# 808_handclap.net
KiCad netlist of a schematic drawn in EAGLE
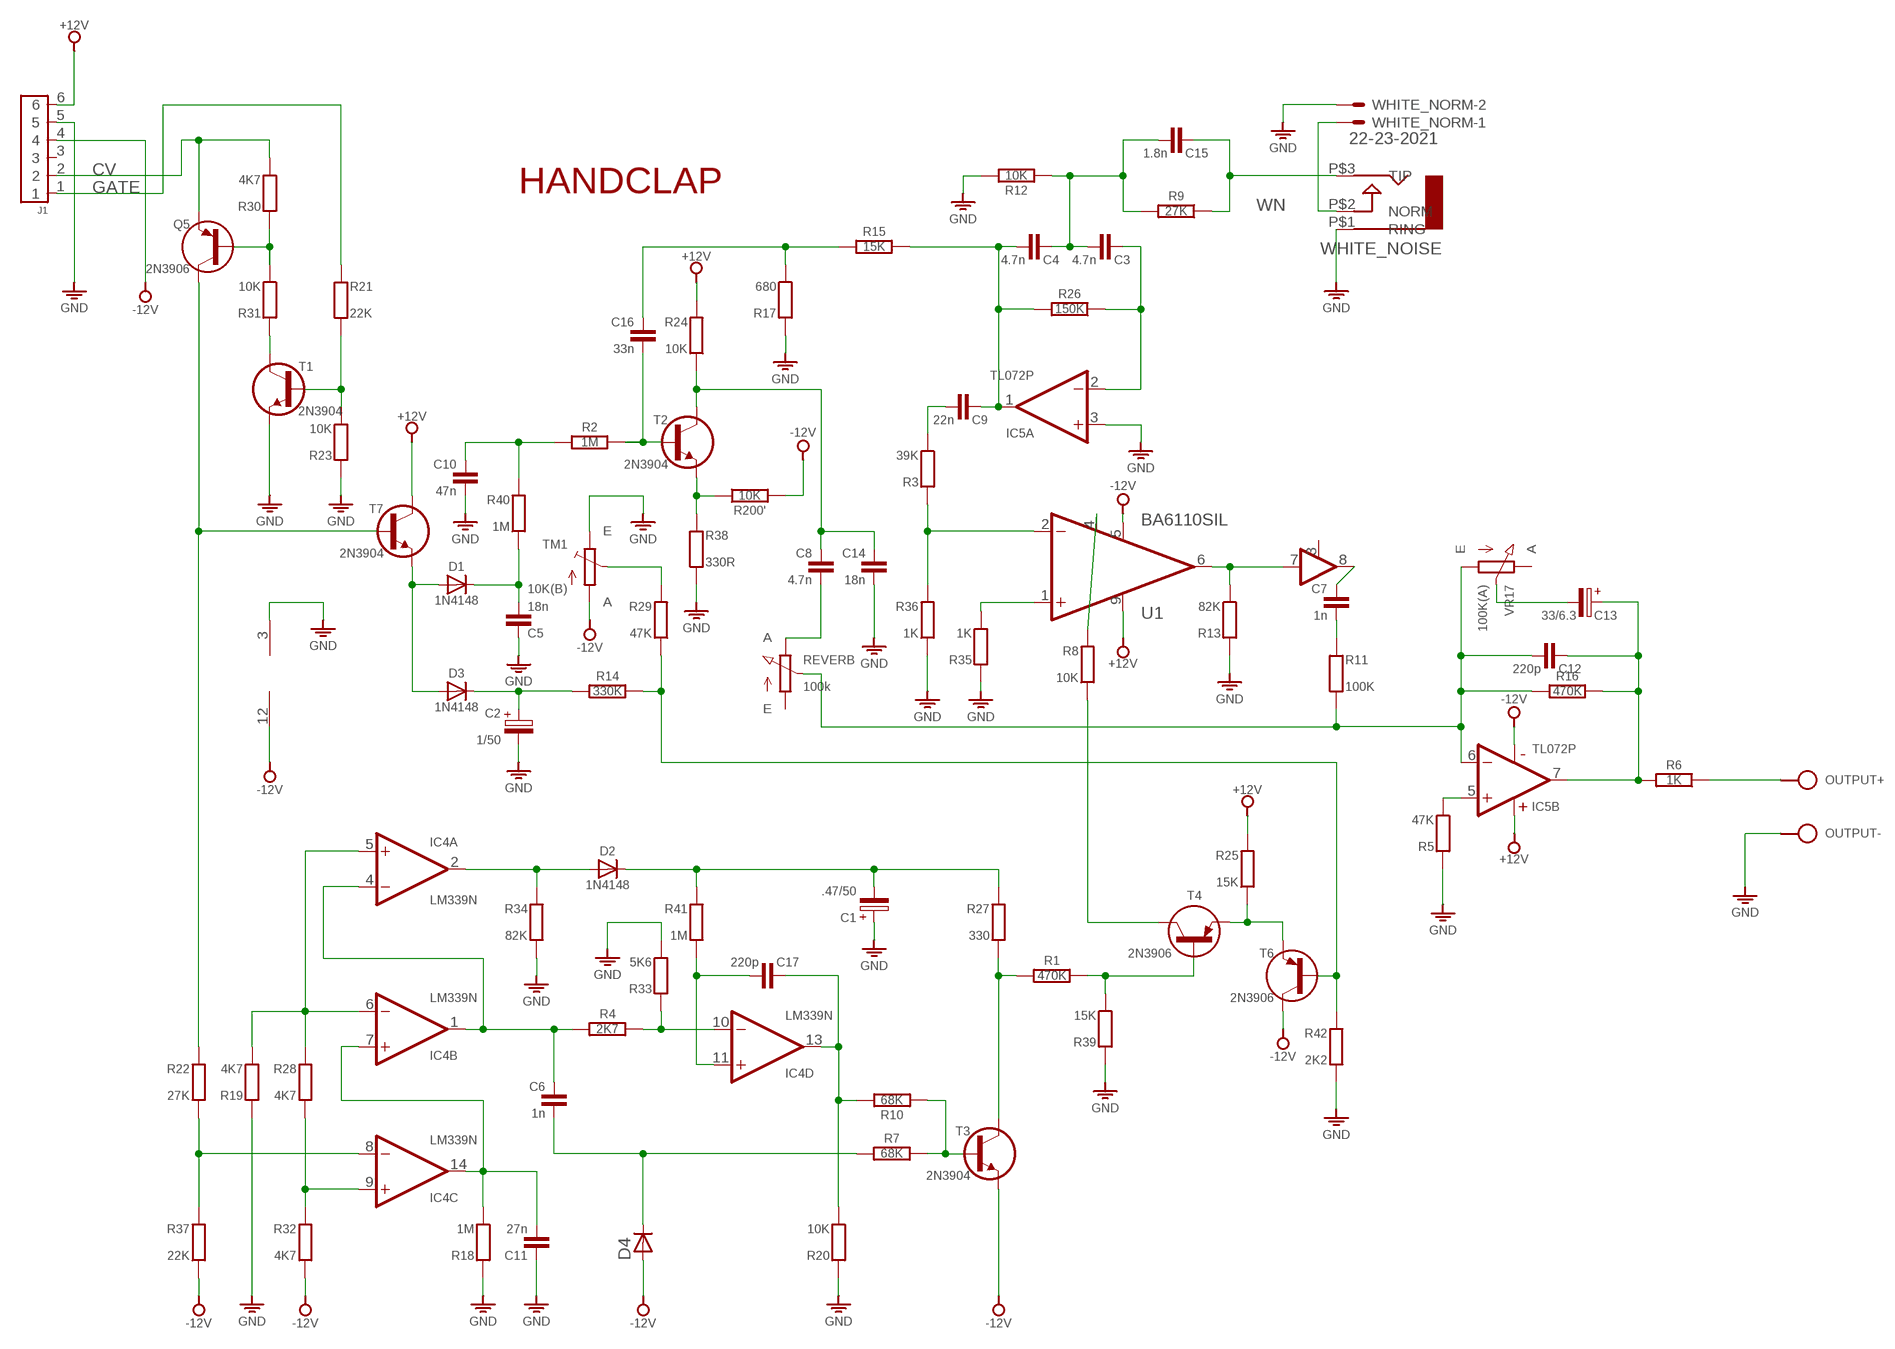
[diagram p0: schematic, sheet 1]

(export (version "E")
  (design (tool "Eeschema 10.0.6"))
  (components
    (comp (ref "C1")
      (value ".47/50")
      (footprint "eagle-import:E2,5-3_V")
      (libsource (lib "eagle-import") (part "CPOLE2,5-3/V"))
    )
    (comp (ref "C2")
      (value "1/50")
      (footprint "eagle-import:E2.5-4_V")
      (libsource (lib "eagle-import") (part "CPOLE2,5-4/V"))
    )
    (comp (ref "C3")
      (value "4.7n")
      (footprint "eagle-import:C050-020X044")
      (libsource (lib "eagle-import") (part "C-H050-020X044"))
    )
    (comp (ref "C4")
      (value "4.7n")
      (footprint "eagle-import:C050-020X044")
      (libsource (lib "eagle-import") (part "C-H050-020X044"))
    )
    (comp (ref "C5")
      (value "18n")
      (footprint "eagle-import:C050-020X044_V")
      (libsource (lib "eagle-import") (part "C050-020X044/V"))
    )
    (comp (ref "C6")
      (value "1n")
      (footprint "eagle-import:C050-020X044_V")
      (libsource (lib "eagle-import") (part "C050-020X044/V"))
    )
    (comp (ref "C7")
      (value "1n")
      (footprint "eagle-import:C050-020X044_V")
      (libsource (lib "eagle-import") (part "C050-020X044/V"))
    )
    (comp (ref "C8")
      (value "4.7n")
      (footprint "eagle-import:C050-020X044_V")
      (libsource (lib "eagle-import") (part "C050-020X044/V"))
    )
    (comp (ref "C9")
      (value "22n")
      (footprint "eagle-import:C050-020X044")
      (libsource (lib "eagle-import") (part "C-H050-020X044"))
    )
    (comp (ref "C10")
      (value "47n")
      (footprint "eagle-import:C050-020X044_V")
      (libsource (lib "eagle-import") (part "C050-020X044/V"))
    )
    (comp (ref "C11")
      (value "27n")
      (footprint "eagle-import:C050-020X044_V")
      (libsource (lib "eagle-import") (part "C050-020X044/V"))
    )
    (comp (ref "C12")
      (value "220p")
      (footprint "eagle-import:C050-020X044")
      (libsource (lib "eagle-import") (part "C-H050-020X044"))
    )
    (comp (ref "C13")
      (value "33/6.3")
      (footprint "eagle-import:E2,5-3")
      (libsource (lib "eagle-import") (part "CPOL-HE2,5-3"))
    )
    (comp (ref "C14")
      (value "18n")
      (footprint "eagle-import:C050-020X044_V")
      (libsource (lib "eagle-import") (part "C050-020X044/V"))
    )
    (comp (ref "C15")
      (value "1.8n")
      (footprint "eagle-import:C050-020X044")
      (libsource (lib "eagle-import") (part "C-H050-020X044"))
    )
    (comp (ref "C16")
      (value "33n")
      (footprint "eagle-import:C050-020X044_V")
      (libsource (lib "eagle-import") (part "C050-020X044/V"))
    )
    (comp (ref "C17")
      (value "220p")
      (footprint "eagle-import:C050-020X044")
      (libsource (lib "eagle-import") (part "C-H050-020X044"))
    )
    (comp (ref "D1")
      (value "1N4148")
      (footprint "eagle-import:DO34-10")
      (libsource (lib "eagle-import") (part "DIODE-HDO34-10"))
    )
    (comp (ref "D2")
      (value "1N4148")
      (footprint "eagle-import:DO34-10")
      (libsource (lib "eagle-import") (part "DIODE-HDO34-10"))
    )
    (comp (ref "D3")
      (value "1N4148")
      (footprint "eagle-import:DO34-10")
      (libsource (lib "eagle-import") (part "DIODE-HDO34-10"))
    )
    (comp (ref "D4")
      (value "1N4148DO35-7")
      (footprint "eagle-import:DO35-7")
      (libsource (lib "eagle-import") (part "1N4148DO35-7"))
    )
    (comp (ref "IC3")
      (value "LM339N")
      (footprint "eagle-import:DIL14")
      (libsource (lib "eagle-import") (part "linear_LM339N"))
    )
    (comp (ref "IC4")
      (value "LM339N")
      (footprint "eagle-import:DIL14")
      (libsource (lib "eagle-import") (part "LM339N"))
    )
    (comp (ref "IC5")
      (value "TL072P")
      (footprint "eagle-import:DIL08")
      (libsource (lib "eagle-import") (part "TL072P"))
    )
    (comp (ref "J1")
      (value "CONN-6P")
      (footprint "eagle-import:CONN-6P")
      (libsource (lib "eagle-import") (part "CONN-6P"))
    )
    (comp (ref "OUTPUT")
      (value "SPAD+-+-")
      (footprint "eagle-import:SPAD+-")
      (libsource (lib "eagle-import") (part "SPAD+-+-"))
    )
    (comp (ref "Q5")
      (value "2N3906")
      (footprint "eagle-import:TO92")
      (libsource (lib "eagle-import") (part "2N3906"))
    )
    (comp (ref "R1")
      (value "470K")
      (footprint "eagle-import:0204_10")
      (libsource (lib "eagle-import") (part "R-H0204/10"))
    )
    (comp (ref "R2")
      (value "1M")
      (footprint "eagle-import:0204_10")
      (libsource (lib "eagle-import") (part "R-H0204/10"))
    )
    (comp (ref "R3")
      (value "39K")
      (footprint "eagle-import:0204_10-V")
      (libsource (lib "eagle-import") (part "R0204/10-V"))
    )
    (comp (ref "R4")
      (value "2K7")
      (footprint "eagle-import:0204_10")
      (libsource (lib "eagle-import") (part "R-H0204/10"))
    )
    (comp (ref "R5")
      (value "47K")
      (footprint "eagle-import:0204_10-V")
      (libsource (lib "eagle-import") (part "R0204/10-V"))
    )
    (comp (ref "R6")
      (value "1K")
      (footprint "eagle-import:0204_10")
      (libsource (lib "eagle-import") (part "R-H0204/10"))
    )
    (comp (ref "R7")
      (value "68K")
      (footprint "eagle-import:0204_10")
      (libsource (lib "eagle-import") (part "R-H0204/10"))
    )
    (comp (ref "R8")
      (value "10K")
      (footprint "eagle-import:0204_10-V")
      (libsource (lib "eagle-import") (part "R0204/10-V"))
    )
    (comp (ref "R9")
      (value "27K")
      (footprint "eagle-import:0204_10")
      (libsource (lib "eagle-import") (part "R-H0204/10"))
    )
    (comp (ref "R10")
      (value "68K")
      (footprint "eagle-import:0204_10")
      (libsource (lib "eagle-import") (part "R-H0204/10"))
    )
    (comp (ref "R11")
      (value "100K")
      (footprint "eagle-import:0204_10-V")
      (libsource (lib "eagle-import") (part "R0204/10-V"))
    )
    (comp (ref "R12")
      (value "10K")
      (footprint "eagle-import:0204_10")
      (libsource (lib "eagle-import") (part "R-H0204/10"))
    )
    (comp (ref "R13")
      (value "82K")
      (footprint "eagle-import:0204_10-V")
      (libsource (lib "eagle-import") (part "R0204/10-V"))
    )
    (comp (ref "R14")
      (value "330K")
      (footprint "eagle-import:0204_10")
      (libsource (lib "eagle-import") (part "R-H0204/10"))
    )
    (comp (ref "R15")
      (value "15K")
      (footprint "eagle-import:0204_10")
      (libsource (lib "eagle-import") (part "R-H0204/10"))
    )
    (comp (ref "R16")
      (value "470K")
      (footprint "eagle-import:0204_10")
      (libsource (lib "eagle-import") (part "R-H0204/10"))
    )
    (comp (ref "R17")
      (value "680")
      (footprint "eagle-import:0204_10-V")
      (libsource (lib "eagle-import") (part "R0204/10-V"))
    )
    (comp (ref "R18")
      (value "1M")
      (footprint "eagle-import:0204_10-V")
      (libsource (lib "eagle-import") (part "R0204/10-V"))
    )
    (comp (ref "R19")
      (value "4K7")
      (footprint "eagle-import:0204_10-V")
      (libsource (lib "eagle-import") (part "R0204/10-V"))
    )
    (comp (ref "R20")
      (value "10K")
      (footprint "eagle-import:0204_10-V")
      (libsource (lib "eagle-import") (part "R0204/10-V"))
    )
    (comp (ref "R21")
      (value "22K")
      (footprint "eagle-import:0204_10-V")
      (libsource (lib "eagle-import") (part "R0204/10-V"))
    )
    (comp (ref "R22")
      (value "27K")
      (footprint "eagle-import:0204_10-V")
      (libsource (lib "eagle-import") (part "R0204/10-V"))
    )
    (comp (ref "R23")
      (value "10K")
      (footprint "eagle-import:0204_10-V")
      (libsource (lib "eagle-import") (part "R0204/10-V"))
    )
    (comp (ref "R24")
      (value "10K")
      (footprint "eagle-import:0204_10-V")
      (libsource (lib "eagle-import") (part "R0204/10-V"))
    )
    (comp (ref "R25")
      (value "15K")
      (footprint "eagle-import:0204_10-V")
      (libsource (lib "eagle-import") (part "R0204/10-V"))
    )
    (comp (ref "R26")
      (value "150K")
      (footprint "eagle-import:0204_10")
      (libsource (lib "eagle-import") (part "R-H0204/10"))
    )
    (comp (ref "R27")
      (value "330")
      (footprint "eagle-import:0204_10-V")
      (libsource (lib "eagle-import") (part "R0204/10-V"))
    )
    (comp (ref "R28")
      (value "4K7")
      (footprint "eagle-import:0204_10-V")
      (libsource (lib "eagle-import") (part "R0204/10-V"))
    )
    (comp (ref "R29")
      (value "47K")
      (footprint "eagle-import:0204_10-V")
      (libsource (lib "eagle-import") (part "R0204/10-V"))
    )
    (comp (ref "R30")
      (value "4K7")
      (footprint "eagle-import:0204_10-V")
      (libsource (lib "eagle-import") (part "R0204/10-V"))
    )
    (comp (ref "R31")
      (value "10K")
      (footprint "eagle-import:0204_10-V")
      (libsource (lib "eagle-import") (part "R0204/10-V"))
    )
    (comp (ref "R32")
      (value "4K7")
      (footprint "eagle-import:0204_10-V")
      (libsource (lib "eagle-import") (part "R0204/10-V"))
    )
    (comp (ref "R33")
      (value "5K6")
      (footprint "eagle-import:0204_10-V")
      (libsource (lib "eagle-import") (part "R0204/10-V"))
    )
    (comp (ref "R34")
      (value "82K")
      (footprint "eagle-import:0204_10-V")
      (libsource (lib "eagle-import") (part "R0204/10-V"))
    )
    (comp (ref "R35")
      (value "1K")
      (footprint "eagle-import:0204_10-V")
      (libsource (lib "eagle-import") (part "R0204/10-V"))
    )
    (comp (ref "R36")
      (value "1K")
      (footprint "eagle-import:0204_10-V")
      (libsource (lib "eagle-import") (part "R0204/10-V"))
    )
    (comp (ref "R37")
      (value "22K")
      (footprint "eagle-import:0204_10-V")
      (libsource (lib "eagle-import") (part "R0204/10-V"))
    )
    (comp (ref "R38")
      (value "330R")
      (footprint "eagle-import:0204_10-V")
      (libsource (lib "eagle-import") (part "R0204/10-V"))
    )
    (comp (ref "R39")
      (value "15K")
      (footprint "eagle-import:0204_10-V")
      (libsource (lib "eagle-import") (part "R0204/10-V"))
    )
    (comp (ref "R40")
      (value "1M")
      (footprint "eagle-import:0204_10-V")
      (libsource (lib "eagle-import") (part "R0204/10-V"))
    )
    (comp (ref "R41")
      (value "1M")
      (footprint "eagle-import:0204_10-V")
      (libsource (lib "eagle-import") (part "R0204/10-V"))
    )
    (comp (ref "R42")
      (value "2K2")
      (footprint "eagle-import:0204_10-V")
      (libsource (lib "eagle-import") (part "R0204/10-V"))
    )
    (comp (ref "R200'")
      (value "10K")
      (footprint "eagle-import:0204_10")
      (libsource (lib "eagle-import") (part "R-H0204/10"))
    )
    (comp (ref "REVERB")
      (value "100k")
      (footprint "eagle-import:POT")
      (libsource (lib "eagle-import") (part "POT"))
    )
    (comp (ref "T1")
      (value "2N3904")
      (footprint "eagle-import:TO92")
      (libsource (lib "eagle-import") (part "2N3904"))
    )
    (comp (ref "T2")
      (value "2N3904")
      (footprint "eagle-import:TO92")
      (libsource (lib "eagle-import") (part "2N3904"))
    )
    (comp (ref "T3")
      (value "2N3904")
      (footprint "eagle-import:TO92")
      (libsource (lib "eagle-import") (part "2N3904"))
    )
    (comp (ref "T4")
      (value "2N3906")
      (footprint "eagle-import:TO92")
      (libsource (lib "eagle-import") (part "2N3906-H"))
    )
    (comp (ref "T6")
      (value "2N3906")
      (footprint "eagle-import:TO92")
      (libsource (lib "eagle-import") (part "2N3906"))
    )
    (comp (ref "T7")
      (value "2N3904")
      (footprint "eagle-import:TO92")
      (libsource (lib "eagle-import") (part "2N3904"))
    )
    (comp (ref "TM1")
      (value "10K(B)")
      (footprint "eagle-import:R-TRIM")
      (libsource (lib "eagle-import") (part "TRIMR-TRIM"))
    )
    (comp (ref "U1")
      (value "BA6110SIL")
      (footprint "eagle-import:SIL09")
      (libsource (lib "eagle-import") (part "BA6110SIL"))
    )
    (comp (ref "VR17")
      (value "100K(A)")
      (footprint "eagle-import:POT")
      (libsource (lib "eagle-import") (part "POT"))
    )
    (comp (ref "WHITE_NOISE")
      (value "AUDIO-JACK")
      (footprint "eagle-import:ERTHENVAR-JACK-90DEG")
      (libsource (lib "eagle-import") (part "AUDIO-JACK"))
    )
    (comp (ref "WHITE_NORM")
      (value "22-23-2021")
      (footprint "eagle-import:22-23-2021")
      (fields (field (name "MF") "MOLEX"))
      (libsource (lib "eagle-import") (part "22-23-2021"))
    )
  )
  (nets
    (net (code "1") (name "+12V") (class "Default")
      (node (ref "IC5") (pin "8") (pinfunction "V+_8") (pintype "power_in"))
      (node (ref "J1") (pin "6") (pinfunction "6_6") (pintype "bidirectional"))
      (node (ref "R24") (pin "1") (pinfunction "1_1") (pintype "passive"))
      (node (ref "R25") (pin "1") (pinfunction "1_1") (pintype "passive"))
      (node (ref "T7") (pin "3") (pinfunction "C_3") (pintype "passive"))
      (node (ref "U1") (pin "9") (pinfunction "V+_9") (pintype "bidirectional"))
    )
    (net (code "2") (name "-12V") (class "Default")
      (node (ref "D4") (pin "A") (pinfunction "A_A") (pintype "passive"))
      (node (ref "IC3") (pin "12") (pinfunction "GND_12") (pintype "power_in"))
      (node (ref "IC5") (pin "4") (pinfunction "V-_4") (pintype "power_in"))
      (node (ref "J1") (pin "4") (pinfunction "4_4") (pintype "bidirectional"))
      (node (ref "R200'") (pin "2") (pinfunction "2_2") (pintype "passive"))
      (node (ref "R32") (pin "2") (pinfunction "2_2") (pintype "passive"))
      (node (ref "R37") (pin "2") (pinfunction "2_2") (pintype "passive"))
      (node (ref "T3") (pin "1") (pinfunction "E_1") (pintype "passive"))
      (node (ref "T6") (pin "3") (pinfunction "C_3") (pintype "passive"))
      (node (ref "TM1") (pin "1") (pinfunction "A_1") (pintype "passive"))
      (node (ref "U1") (pin "5") (pinfunction "V-_5") (pintype "bidirectional"))
    )
    (net (code "3") (name "/CV") (class "Default")
      (node (ref "J1") (pin "2") (pinfunction "2_2") (pintype "bidirectional"))
      (node (ref "Q5") (pin "1") (pinfunction "E_1") (pintype "passive"))
      (node (ref "R30") (pin "2") (pinfunction "2_2") (pintype "passive"))
    )
    (net (code "4") (name "/GATE") (class "Default")
      (node (ref "J1") (pin "1") (pinfunction "1_1") (pintype "bidirectional"))
      (node (ref "R21") (pin "1") (pinfunction "1_1") (pintype "passive"))
    )
    (net (code "5") (name "/WN") (class "Default")
      (node (ref "C15") (pin "1") (pinfunction "1_1") (pintype "passive"))
      (node (ref "R9") (pin "1") (pinfunction "1_1") (pintype "passive"))
      (node (ref "WHITE_NOISE") (pin "P$3") (pinfunction "TIP_P$3") (pintype "bidirectional"))
    )
    (net (code "6") (name "GND") (class "Default")
      (node (ref "C1") (pin "+") (pinfunction "+_+") (pintype "passive"))
      (node (ref "C10") (pin "2") (pinfunction "2_2") (pintype "passive"))
      (node (ref "C11") (pin "1") (pinfunction "1_1") (pintype "passive"))
      (node (ref "C14") (pin "2") (pinfunction "2_2") (pintype "passive"))
      (node (ref "C2") (pin "-") (pinfunction "-_-") (pintype "passive"))
      (node (ref "C5") (pin "1") (pinfunction "1_1") (pintype "passive"))
      (node (ref "IC3") (pin "3") (pinfunction "V+_3") (pintype "power_in"))
      (node (ref "IC5") (pin "3") (pinfunction "+IN_3") (pintype "input"))
      (node (ref "J1") (pin "5") (pinfunction "5_5") (pintype "bidirectional"))
      (node (ref "OUTPUT") (pin "1") (pinfunction "P$1_1") (pintype "passive"))
      (node (ref "R12") (pin "1") (pinfunction "1_1") (pintype "passive"))
      (node (ref "R13") (pin "1") (pinfunction "1_1") (pintype "passive"))
      (node (ref "R17") (pin "1") (pinfunction "1_1") (pintype "passive"))
      (node (ref "R18") (pin "1") (pinfunction "1_1") (pintype "passive"))
      (node (ref "R19") (pin "1") (pinfunction "1_1") (pintype "passive"))
      (node (ref "R20") (pin "1") (pinfunction "1_1") (pintype "passive"))
      (node (ref "R23") (pin "1") (pinfunction "1_1") (pintype "passive"))
      (node (ref "R33") (pin "2") (pinfunction "2_2") (pintype "passive"))
      (node (ref "R34") (pin "2") (pinfunction "2_2") (pintype "passive"))
      (node (ref "R35") (pin "1") (pinfunction "1_1") (pintype "passive"))
      (node (ref "R36") (pin "2") (pinfunction "2_2") (pintype "passive"))
      (node (ref "R38") (pin "2") (pinfunction "2_2") (pintype "passive"))
      (node (ref "R39") (pin "1") (pinfunction "1_1") (pintype "passive"))
      (node (ref "R42") (pin "2") (pinfunction "2_2") (pintype "passive"))
      (node (ref "R5") (pin "1") (pinfunction "1_1") (pintype "passive"))
      (node (ref "T1") (pin "1") (pinfunction "E_1") (pintype "passive"))
      (node (ref "TM1") (pin "3") (pinfunction "E_3") (pintype "passive"))
      (node (ref "WHITE_NOISE") (pin "P$1") (pinfunction "RING_P$1") (pintype "bidirectional"))
      (node (ref "WHITE_NORM") (pin "2") (pinfunction "S_2") (pintype "passive"))
    )
    (net (code "7") (name "Net-(C1-Pad-)") (class "Default")
      (node (ref "C1") (pin "-") (pinfunction "-_-") (pintype "passive"))
      (node (ref "D2") (pin "C") (pinfunction "C_C") (pintype "passive"))
      (node (ref "R27") (pin "1") (pinfunction "1_1") (pintype "passive"))
      (node (ref "R41") (pin "1") (pinfunction "1_1") (pintype "passive"))
    )
    (net (code "8") (name "Net-(C2-Pad+)") (class "Default")
      (node (ref "C2") (pin "+") (pinfunction "+_+") (pintype "passive"))
      (node (ref "D3") (pin "C") (pinfunction "C_C") (pintype "passive"))
      (node (ref "R14") (pin "2") (pinfunction "2_2") (pintype "passive"))
    )
    (net (code "9") (name "Net-(C5-Pad2)") (class "Default")
      (node (ref "C5") (pin "2") (pinfunction "2_2") (pintype "passive"))
      (node (ref "D1") (pin "C") (pinfunction "C_C") (pintype "passive"))
      (node (ref "R40") (pin "2") (pinfunction "2_2") (pintype "passive"))
    )
    (net (code "10") (name "Net-(C6-Pad2)") (class "Default")
      (node (ref "C6") (pin "2") (pinfunction "2_2") (pintype "passive"))
      (node (ref "D4") (pin "C") (pinfunction "C_C") (pintype "passive"))
      (node (ref "R7") (pin "2") (pinfunction "2_2") (pintype "passive"))
    )
    (net (code "11") (name "Net-(C7-Pad2)") (class "Default")
      (node (ref "C7") (pin "2") (pinfunction "2_2") (pintype "passive"))
      (node (ref "R11") (pin "1") (pinfunction "1_1") (pintype "passive"))
    )
    (net (code "12") (name "Net-(C8-Pad2)") (class "Default")
      (node (ref "C8") (pin "2") (pinfunction "2_2") (pintype "passive"))
      (node (ref "REVERB") (pin "E") (pinfunction "E_E") (pintype "passive"))
    )
    (net (code "13") (name "Net-(C9-Pad2)") (class "Default")
      (node (ref "C9") (pin "2") (pinfunction "2_2") (pintype "passive"))
      (node (ref "R3") (pin "2") (pinfunction "2_2") (pintype "passive"))
    )
    (net (code "14") (name "Net-(C10-Pad1)") (class "Default")
      (node (ref "C10") (pin "1") (pinfunction "1_1") (pintype "passive"))
      (node (ref "R2") (pin "2") (pinfunction "2_2") (pintype "passive"))
      (node (ref "R40") (pin "1") (pinfunction "1_1") (pintype "passive"))
    )
    (net (code "15") (name "Net-(C13-Pad-)") (class "Default")
      (node (ref "C13") (pin "-") (pinfunction "-_-") (pintype "passive"))
      (node (ref "VR17") (pin "S") (pinfunction "S_S") (pintype "passive"))
    )
    (net (code "16") (name "Net-(C15-Pad2)") (class "Default")
      (node (ref "C15") (pin "2") (pinfunction "2_2") (pintype "passive"))
      (node (ref "C3") (pin "2") (pinfunction "2_2") (pintype "passive"))
      (node (ref "C4") (pin "1") (pinfunction "1_1") (pintype "passive"))
      (node (ref "R12") (pin "2") (pinfunction "2_2") (pintype "passive"))
      (node (ref "R9") (pin "2") (pinfunction "2_2") (pintype "passive"))
    )
    (net (code "17") (name "Net-(C16-Pad1)") (class "Default")
      (node (ref "C16") (pin "1") (pinfunction "1_1") (pintype "passive"))
      (node (ref "R15") (pin "2") (pinfunction "2_2") (pintype "passive"))
      (node (ref "R17") (pin "2") (pinfunction "2_2") (pintype "passive"))
    )
    (net (code "18") (name "Net-(IC4B-+IN)") (class "Default")
      (node (ref "IC4") (pin "5") (pinfunction "+IN_5") (pintype "input"))
      (node (ref "IC4") (pin "6") (pinfunction "-IN_6") (pintype "input"))
      (node (ref "R19") (pin "2") (pinfunction "2_2") (pintype "passive"))
      (node (ref "R28") (pin "1") (pinfunction "1_1") (pintype "passive"))
    )
    (net (code "19") (name "Net-(IC4B--IN)") (class "Default")
      (node (ref "C6") (pin "1") (pinfunction "1_1") (pintype "passive"))
      (node (ref "IC4") (pin "1") (pinfunction "OUT_1") (pintype "output"))
      (node (ref "IC4") (pin "4") (pinfunction "-IN_4") (pintype "input"))
      (node (ref "R4") (pin "2") (pinfunction "2_2") (pintype "passive"))
    )
    (net (code "20") (name "Net-(IC4B-OUT)") (class "Default")
      (node (ref "D2") (pin "A") (pinfunction "A_A") (pintype "passive"))
      (node (ref "IC4") (pin "2") (pinfunction "OUT_2") (pintype "output"))
      (node (ref "R34") (pin "1") (pinfunction "1_1") (pintype "passive"))
    )
    (net (code "21") (name "Net-(IC4C-+IN)") (class "Default")
      (node (ref "C11") (pin "2") (pinfunction "2_2") (pintype "passive"))
      (node (ref "IC4") (pin "14") (pinfunction "OUT_14") (pintype "output"))
      (node (ref "IC4") (pin "7") (pinfunction "+IN_7") (pintype "input"))
      (node (ref "R18") (pin "2") (pinfunction "2_2") (pintype "passive"))
    )
    (net (code "22") (name "Net-(IC4D-+IN)") (class "Default")
      (node (ref "IC4") (pin "9") (pinfunction "+IN_9") (pintype "input"))
      (node (ref "R28") (pin "2") (pinfunction "2_2") (pintype "passive"))
      (node (ref "R32") (pin "1") (pinfunction "1_1") (pintype "passive"))
    )
    (net (code "23") (name "Net-(IC4D--IN)") (class "Default")
      (node (ref "IC4") (pin "8") (pinfunction "-IN_8") (pintype "input"))
      (node (ref "R22") (pin "2") (pinfunction "2_2") (pintype "passive"))
      (node (ref "R37") (pin "1") (pinfunction "1_1") (pintype "passive"))
    )
    (net (code "24") (name "Net-(IC4E-+IN)") (class "Default")
      (node (ref "C17") (pin "2") (pinfunction "2_2") (pintype "passive"))
      (node (ref "IC4") (pin "11") (pinfunction "+IN_11") (pintype "input"))
      (node (ref "R41") (pin "2") (pinfunction "2_2") (pintype "passive"))
    )
    (net (code "25") (name "Net-(IC4E--IN)") (class "Default")
      (node (ref "IC4") (pin "10") (pinfunction "-IN_10") (pintype "input"))
      (node (ref "R33") (pin "1") (pinfunction "1_1") (pintype "passive"))
      (node (ref "R4") (pin "1") (pinfunction "1_1") (pintype "passive"))
    )
    (net (code "26") (name "Net-(IC4E-OUT)") (class "Default")
      (node (ref "C17") (pin "1") (pinfunction "1_1") (pintype "passive"))
      (node (ref "IC4") (pin "13") (pinfunction "OUT_13") (pintype "output"))
      (node (ref "R10") (pin "1") (pinfunction "1_1") (pintype "passive"))
      (node (ref "R20") (pin "2") (pinfunction "2_2") (pintype "passive"))
    )
    (net (code "27") (name "Net-(IC5A--IN)") (class "Default")
      (node (ref "C3") (pin "1") (pinfunction "1_1") (pintype "passive"))
      (node (ref "IC5") (pin "2") (pinfunction "-IN_2") (pintype "input"))
      (node (ref "R26") (pin "1") (pinfunction "1_1") (pintype "passive"))
    )
    (net (code "28") (name "Net-(IC5A-OUT)") (class "Default")
      (node (ref "C4") (pin "2") (pinfunction "2_2") (pintype "passive"))
      (node (ref "C9") (pin "1") (pinfunction "1_1") (pintype "passive"))
      (node (ref "IC5") (pin "1") (pinfunction "OUT_1") (pintype "output"))
      (node (ref "R15") (pin "1") (pinfunction "1_1") (pintype "passive"))
      (node (ref "R26") (pin "2") (pinfunction "2_2") (pintype "passive"))
    )
    (net (code "29") (name "Net-(IC5B-+IN)") (class "Default")
      (node (ref "IC5") (pin "5") (pinfunction "+IN_5") (pintype "input"))
      (node (ref "R5") (pin "2") (pinfunction "2_2") (pintype "passive"))
    )
    (net (code "30") (name "Net-(IC5B--IN)") (class "Default")
      (node (ref "C12") (pin "2") (pinfunction "2_2") (pintype "passive"))
      (node (ref "IC5") (pin "6") (pinfunction "-IN_6") (pintype "input"))
      (node (ref "R11") (pin "2") (pinfunction "2_2") (pintype "passive"))
      (node (ref "R16") (pin "2") (pinfunction "2_2") (pintype "passive"))
      (node (ref "REVERB") (pin "S") (pinfunction "S_S") (pintype "passive"))
      (node (ref "VR17") (pin "A") (pinfunction "A_A") (pintype "passive"))
    )
    (net (code "31") (name "Net-(IC5B-OUT)") (class "Default")
      (node (ref "C12") (pin "1") (pinfunction "1_1") (pintype "passive"))
      (node (ref "C13") (pin "+") (pinfunction "+_+") (pintype "passive"))
      (node (ref "IC5") (pin "7") (pinfunction "OUT_7") (pintype "output"))
      (node (ref "R16") (pin "1") (pinfunction "1_1") (pintype "passive"))
      (node (ref "R6") (pin "2") (pinfunction "2_2") (pintype "passive"))
    )
    (net (code "32") (name "Net-(OUTPUTA-P$1)") (class "Default")
      (node (ref "OUTPUT") (pin "2") (pinfunction "P$1_2") (pintype "passive"))
      (node (ref "R6") (pin "1") (pinfunction "1_1") (pintype "passive"))
    )
    (net (code "33") (name "Net-(Q5-B)") (class "Default")
      (node (ref "Q5") (pin "2") (pinfunction "B_2") (pintype "passive"))
      (node (ref "R30") (pin "1") (pinfunction "1_1") (pintype "passive"))
      (node (ref "R31") (pin "2") (pinfunction "2_2") (pintype "passive"))
    )
    (net (code "34") (name "Net-(Q5-C)") (class "Default")
      (node (ref "Q5") (pin "3") (pinfunction "C_3") (pintype "passive"))
      (node (ref "R22") (pin "1") (pinfunction "1_1") (pintype "passive"))
      (node (ref "T7") (pin "2") (pinfunction "B_2") (pintype "passive"))
    )
    (net (code "35") (name "Net-(T1-B)") (class "Default")
      (node (ref "R21") (pin "2") (pinfunction "2_2") (pintype "passive"))
      (node (ref "R23") (pin "2") (pinfunction "2_2") (pintype "passive"))
      (node (ref "T1") (pin "2") (pinfunction "B_2") (pintype "passive"))
    )
    (net (code "36") (name "Net-(T1-C)") (class "Default")
      (node (ref "R31") (pin "1") (pinfunction "1_1") (pintype "passive"))
      (node (ref "T1") (pin "3") (pinfunction "C_3") (pintype "passive"))
    )
    (net (code "37") (name "Net-(T2-B)") (class "Default")
      (node (ref "C16") (pin "2") (pinfunction "2_2") (pintype "passive"))
      (node (ref "R2") (pin "1") (pinfunction "1_1") (pintype "passive"))
      (node (ref "T2") (pin "2") (pinfunction "B_2") (pintype "passive"))
    )
    (net (code "38") (name "Net-(T2-C)") (class "Default")
      (node (ref "C14") (pin "1") (pinfunction "1_1") (pintype "passive"))
      (node (ref "C8") (pin "1") (pinfunction "1_1") (pintype "passive"))
      (node (ref "R24") (pin "2") (pinfunction "2_2") (pintype "passive"))
      (node (ref "T2") (pin "3") (pinfunction "C_3") (pintype "passive"))
    )
    (net (code "39") (name "Net-(T2-E)") (class "Default")
      (node (ref "R200'") (pin "1") (pinfunction "1_1") (pintype "passive"))
      (node (ref "R38") (pin "1") (pinfunction "1_1") (pintype "passive"))
      (node (ref "T2") (pin "1") (pinfunction "E_1") (pintype "passive"))
    )
    (net (code "40") (name "Net-(T3-B)") (class "Default")
      (node (ref "R10") (pin "2") (pinfunction "2_2") (pintype "passive"))
      (node (ref "R7") (pin "1") (pinfunction "1_1") (pintype "passive"))
      (node (ref "T3") (pin "2") (pinfunction "B_2") (pintype "passive"))
    )
    (net (code "41") (name "Net-(T3-C)") (class "Default")
      (node (ref "R1") (pin "2") (pinfunction "2_2") (pintype "passive"))
      (node (ref "R27") (pin "2") (pinfunction "2_2") (pintype "passive"))
      (node (ref "T3") (pin "3") (pinfunction "C_3") (pintype "passive"))
    )
    (net (code "42") (name "Net-(T4-B)") (class "Default")
      (node (ref "R1") (pin "1") (pinfunction "1_1") (pintype "passive"))
      (node (ref "R39") (pin "2") (pinfunction "2_2") (pintype "passive"))
      (node (ref "T4") (pin "2") (pinfunction "B_2") (pintype "passive"))
    )
    (net (code "43") (name "Net-(T4-C)") (class "Default")
      (node (ref "R8") (pin "2") (pinfunction "2_2") (pintype "passive"))
      (node (ref "T4") (pin "3") (pinfunction "C_3") (pintype "passive"))
    )
    (net (code "44") (name "Net-(T4-E)") (class "Default")
      (node (ref "R25") (pin "2") (pinfunction "2_2") (pintype "passive"))
      (node (ref "T4") (pin "1") (pinfunction "E_1") (pintype "passive"))
      (node (ref "T6") (pin "1") (pinfunction "E_1") (pintype "passive"))
    )
    (net (code "45") (name "Net-(T6-B)") (class "Default")
      (node (ref "R14") (pin "1") (pinfunction "1_1") (pintype "passive"))
      (node (ref "R29") (pin "2") (pinfunction "2_2") (pintype "passive"))
      (node (ref "R42") (pin "1") (pinfunction "1_1") (pintype "passive"))
      (node (ref "T6") (pin "2") (pinfunction "B_2") (pintype "passive"))
    )
    (net (code "46") (name "Net-(T7-E)") (class "Default")
      (node (ref "D1") (pin "A") (pinfunction "A_A") (pintype "passive"))
      (node (ref "D3") (pin "A") (pinfunction "A_A") (pintype "passive"))
      (node (ref "T7") (pin "1") (pinfunction "E_1") (pintype "passive"))
    )
    (net (code "47") (name "Net-(TM1-S)") (class "Default")
      (node (ref "R29") (pin "1") (pinfunction "1_1") (pintype "passive"))
      (node (ref "TM1") (pin "2") (pinfunction "S_2") (pintype "passive"))
    )
    (net (code "48") (name "Net-(U1-+IN)") (class "Default")
      (node (ref "R35") (pin "2") (pinfunction "2_2") (pintype "passive"))
      (node (ref "U1") (pin "1") (pinfunction "+IN_1") (pintype "input"))
    )
    (net (code "49") (name "Net-(U1--IN)") (class "Default")
      (node (ref "R3") (pin "1") (pinfunction "1_1") (pintype "passive"))
      (node (ref "R36") (pin "1") (pinfunction "1_1") (pintype "passive"))
      (node (ref "U1") (pin "2") (pinfunction "-IN_2") (pintype "input"))
    )
    (net (code "50") (name "Net-(U1-C)") (class "Default")
      (node (ref "R8") (pin "1") (pinfunction "1_1") (pintype "passive"))
      (node (ref "U1") (pin "4") (pinfunction "C_4") (pintype "bidirectional"))
    )
    (net (code "51") (name "Net-(U1-IN1)") (class "Default")
      (node (ref "R13") (pin "2") (pinfunction "2_2") (pintype "passive"))
      (node (ref "U1") (pin "6") (pinfunction "OUT_6") (pintype "output"))
      (node (ref "U1") (pin "7") (pinfunction "IN1_7") (pintype "input"))
    )
    (net (code "52") (name "Net-(U1-OUT1)") (class "Default")
      (node (ref "C7") (pin "1") (pinfunction "1_1") (pintype "passive"))
      (node (ref "U1") (pin "8") (pinfunction "OUT1_8") (pintype "output"))
    )
    (net (code "53") (name "Net-(WHITE_NOISE-NORM)") (class "Default")
      (node (ref "WHITE_NOISE") (pin "P$2") (pinfunction "NORM_P$2") (pintype "bidirectional"))
      (node (ref "WHITE_NORM") (pin "1") (pinfunction "S_1") (pintype "passive"))
    )
    (net (code "54") (name "unconnected-(J1-Pad3)") (class "Default")
      (node (ref "J1") (pin "3") (pinfunction "3_3") (pintype "bidirectional"))
    )
    (net (code "55") (name "unconnected-(REVERB-PadA)") (class "Default")
      (node (ref "REVERB") (pin "A") (pinfunction "A_A") (pintype "passive"))
    )
    (net (code "56") (name "unconnected-(U1-P$3-Pad3)") (class "Default")
      (node (ref "U1") (pin "3") (pinfunction "P$3_3") (pintype "bidirectional"))
    )
    (net (code "57") (name "unconnected-(VR17-PadE)") (class "Default")
      (node (ref "VR17") (pin "E") (pinfunction "E_E") (pintype "passive"))
    )
  )
)
